# S3220B2.net
KiCad netlist of a schematic drawn in Altium Designer
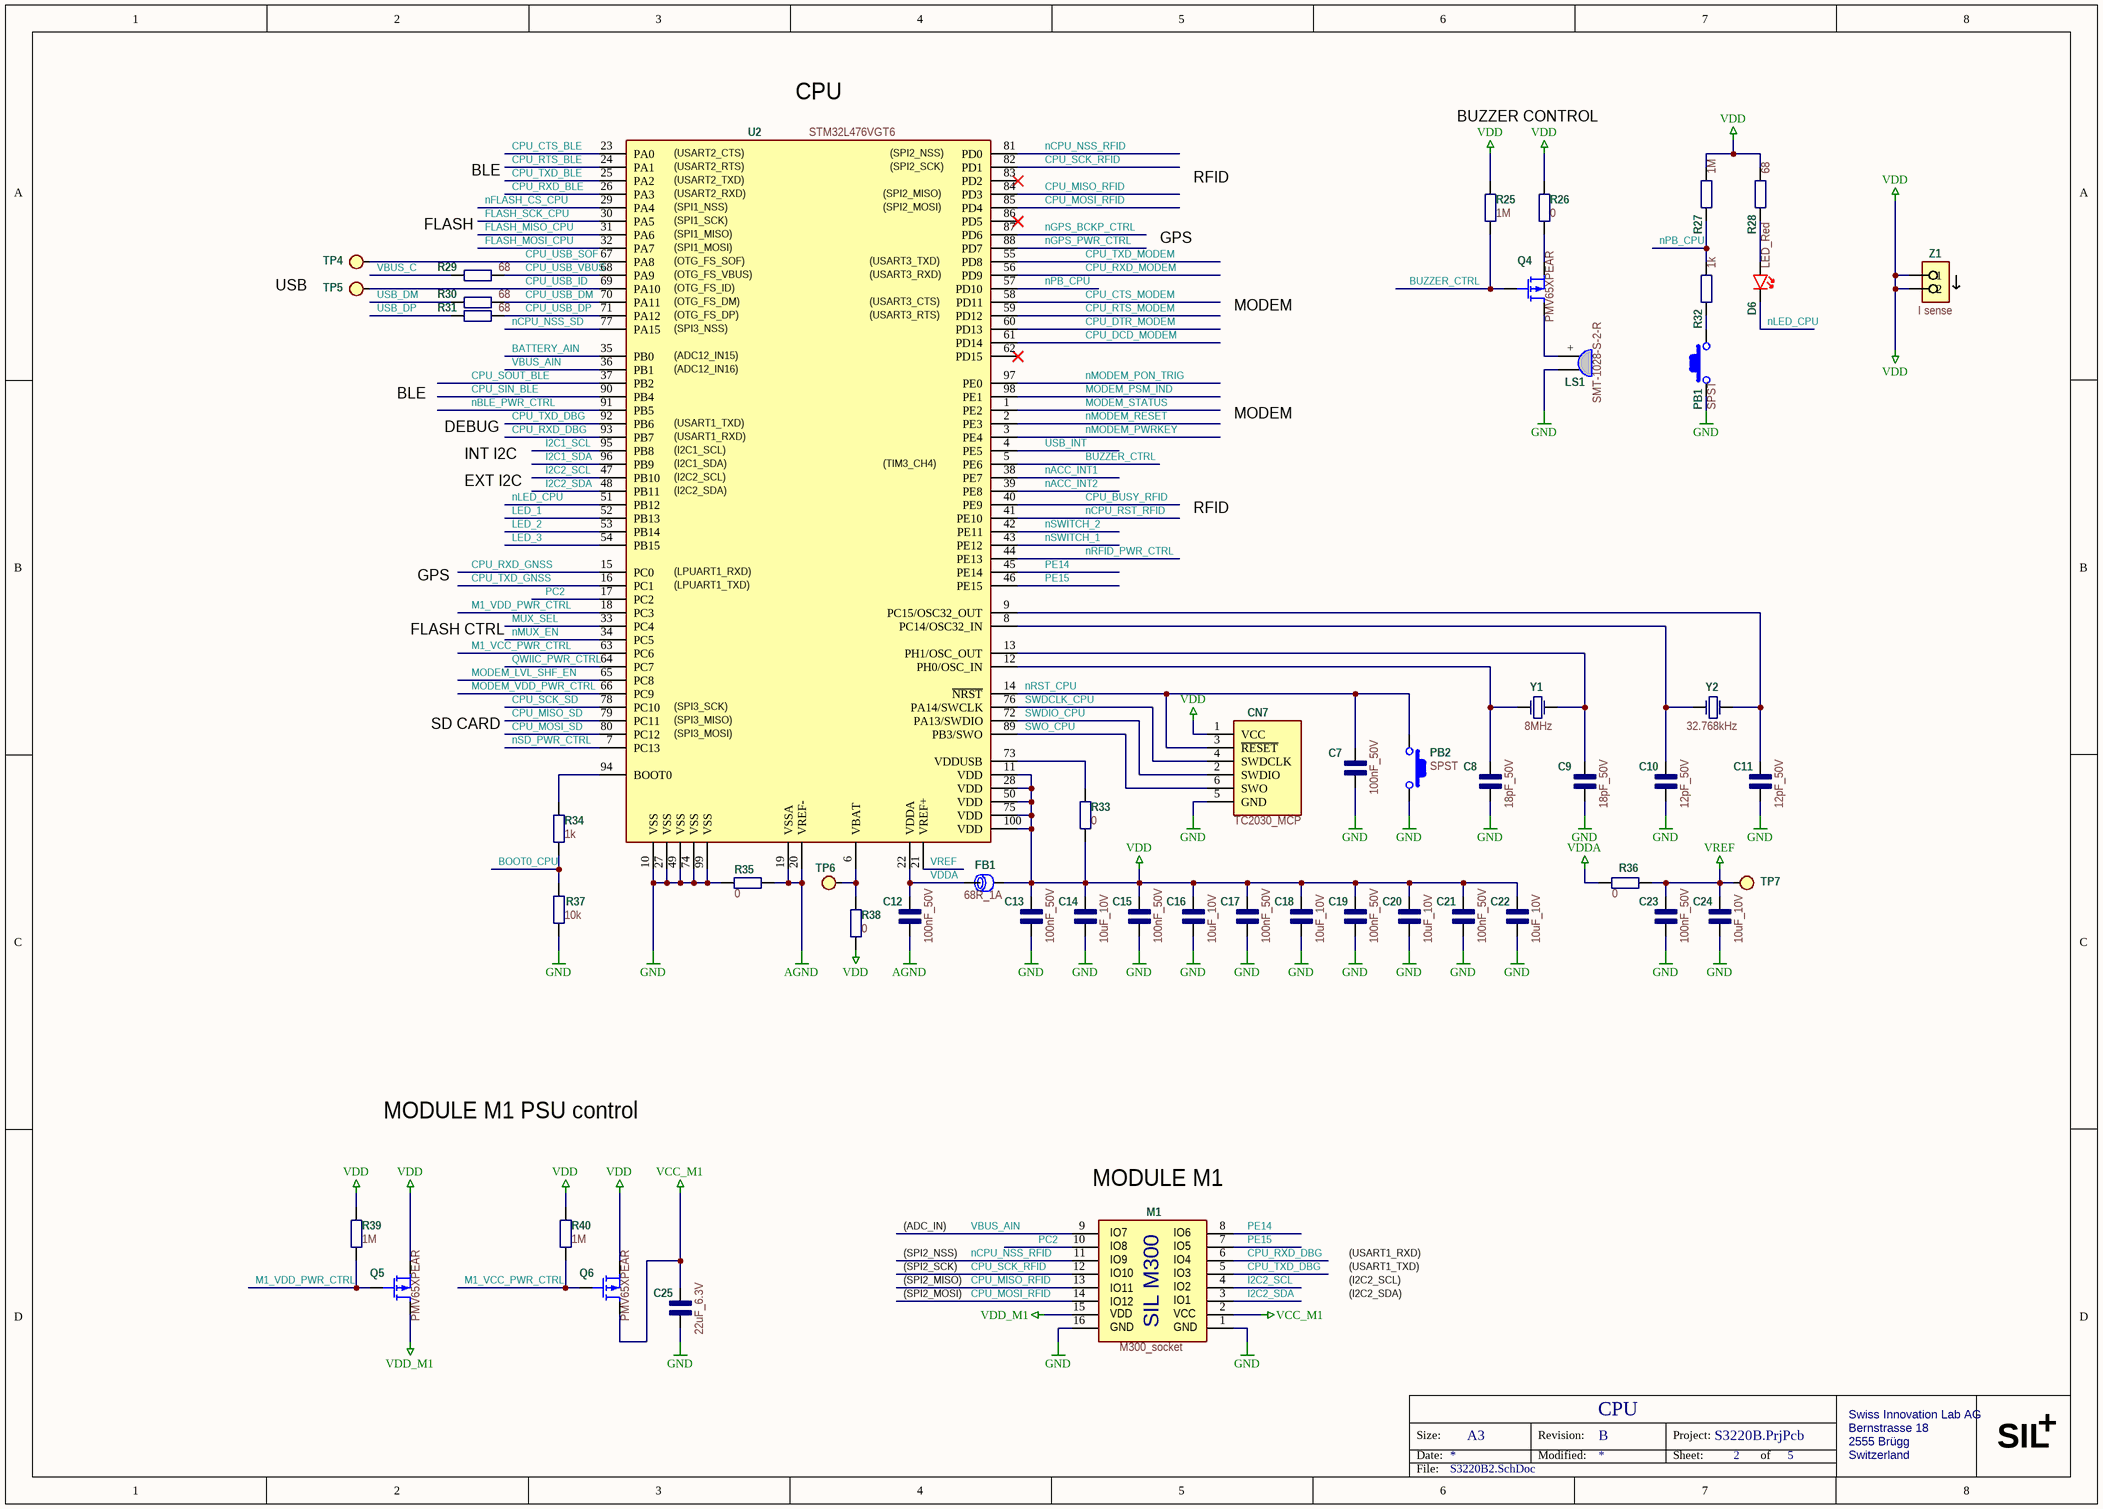
[diagram p0: S3220B2.SchDoc]

(export (version "E")
  (design (tool "Eeschema 10.0.6"))
  (components
    (comp (ref "C7")
      (value "100nF_50V")
      (footprint "SIL:C_0603")
      (description "0.1µF ±10% 50V Ceramic Capacitor X7R 0603 (1608 Metric)")
      (fields
        (field (name "MANUFACTURER") "TDK")
        (field (name "MANUFACTURER PART NUMBER") "C1608X7R1H104K080AA")
      )
      (libsource (lib "SIL") (part "C_100nF_50V"))
    )
    (comp (ref "C8")
      (value "18pF_50V")
      (footprint "SIL:C_0603")
      (description "18pF ±5% 50V Ceramic Capacitor C0G, NP0 0603 (1608 Metric)")
      (fields
        (field (name "MANUFACTURER") "KEMET")
        (field (name "MANUFACTURER PART NUMBER") "C0603C180J5GACTU")
      )
      (libsource (lib "SIL") (part "C_18pF_50V"))
    )
    (comp (ref "C9")
      (value "18pF_50V")
      (footprint "SIL:C_0603")
      (description "18pF ±5% 50V Ceramic Capacitor C0G, NP0 0603 (1608 Metric)")
      (fields
        (field (name "MANUFACTURER") "KEMET")
        (field (name "MANUFACTURER PART NUMBER") "C0603C180J5GACTU")
      )
      (libsource (lib "SIL") (part "C_18pF_50V"))
    )
    (comp (ref "C10")
      (value "12pF_50V")
      (footprint "SIL:C_0603")
      (description "12pF ±1% 50V Ceramic Capacitor C0G, NP0 0603 (1608 Metric)")
      (fields
        (field (name "MANUFACTURER") "Samsung Electro-Mechanics")
        (field (name "MANUFACTURER PART NUMBER") "CL10C120FB8NNNC")
      )
      (libsource (lib "SIL") (part "C_12pF_50V"))
    )
    (comp (ref "C11")
      (value "12pF_50V")
      (footprint "SIL:C_0603")
      (description "12pF ±1% 50V Ceramic Capacitor C0G, NP0 0603 (1608 Metric)")
      (fields
        (field (name "MANUFACTURER") "Samsung Electro-Mechanics")
        (field (name "MANUFACTURER PART NUMBER") "CL10C120FB8NNNC")
      )
      (libsource (lib "SIL") (part "C_12pF_50V"))
    )
    (comp (ref "C12")
      (value "100nF_50V")
      (footprint "SIL:C_0603")
      (description "0.1µF ±10% 50V Ceramic Capacitor X7R 0603 (1608 Metric)")
      (fields
        (field (name "MANUFACTURER") "TDK")
        (field (name "MANUFACTURER PART NUMBER") "C1608X7R1H104K080AA")
      )
      (libsource (lib "SIL") (part "C_100nF_50V"))
    )
    (comp (ref "C13")
      (value "100nF_50V")
      (footprint "SIL:C_0603")
      (description "0.1µF ±10% 50V Ceramic Capacitor X7R 0603 (1608 Metric)")
      (fields
        (field (name "MANUFACTURER") "TDK")
        (field (name "MANUFACTURER PART NUMBER") "C1608X7R1H104K080AA")
      )
      (libsource (lib "SIL") (part "C_100nF_50V"))
    )
    (comp (ref "C14")
      (value "10uF_10V")
      (footprint "SIL:C_0603")
      (description "10µF ±10% 10V Ceramic Capacitor X5R 0603 (1608 Metric)")
      (fields
        (field (name "MANUFACTURER") "Murata Electronics North America")
        (field (name "MANUFACTURER PART NUMBER") "GRM188R61A106KE69D")
      )
      (libsource (lib "SIL") (part "C_10uF_10V"))
    )
    (comp (ref "C15")
      (value "100nF_50V")
      (footprint "SIL:C_0603")
      (description "0.1µF ±10% 50V Ceramic Capacitor X7R 0603 (1608 Metric)")
      (fields
        (field (name "MANUFACTURER") "TDK")
        (field (name "MANUFACTURER PART NUMBER") "C1608X7R1H104K080AA")
      )
      (libsource (lib "SIL") (part "C_100nF_50V"))
    )
    (comp (ref "C16")
      (value "10uF_10V")
      (footprint "SIL:C_0603")
      (description "10µF ±10% 10V Ceramic Capacitor X5R 0603 (1608 Metric)")
      (fields
        (field (name "MANUFACTURER") "Murata Electronics North America")
        (field (name "MANUFACTURER PART NUMBER") "GRM188R61A106KE69D")
      )
      (libsource (lib "SIL") (part "C_10uF_10V"))
    )
    (comp (ref "C17")
      (value "100nF_50V")
      (footprint "SIL:C_0603")
      (description "0.1µF ±10% 50V Ceramic Capacitor X7R 0603 (1608 Metric)")
      (fields
        (field (name "MANUFACTURER") "TDK")
        (field (name "MANUFACTURER PART NUMBER") "C1608X7R1H104K080AA")
      )
      (libsource (lib "SIL") (part "C_100nF_50V"))
    )
    (comp (ref "C18")
      (value "10uF_10V")
      (footprint "SIL:C_0603")
      (description "10µF ±10% 10V Ceramic Capacitor X5R 0603 (1608 Metric)")
      (fields
        (field (name "MANUFACTURER") "Murata Electronics North America")
        (field (name "MANUFACTURER PART NUMBER") "GRM188R61A106KE69D")
      )
      (libsource (lib "SIL") (part "C_10uF_10V"))
    )
    (comp (ref "C19")
      (value "100nF_50V")
      (footprint "SIL:C_0603")
      (description "0.1µF ±10% 50V Ceramic Capacitor X7R 0603 (1608 Metric)")
      (fields
        (field (name "MANUFACTURER") "TDK")
        (field (name "MANUFACTURER PART NUMBER") "C1608X7R1H104K080AA")
      )
      (libsource (lib "SIL") (part "C_100nF_50V"))
    )
    (comp (ref "C20")
      (value "10uF_10V")
      (footprint "SIL:C_0603")
      (description "10µF ±10% 10V Ceramic Capacitor X5R 0603 (1608 Metric)")
      (fields
        (field (name "MANUFACTURER") "Murata Electronics North America")
        (field (name "MANUFACTURER PART NUMBER") "GRM188R61A106KE69D")
      )
      (libsource (lib "SIL") (part "C_10uF_10V"))
    )
    (comp (ref "C21")
      (value "100nF_50V")
      (footprint "SIL:C_0603")
      (description "0.1µF ±10% 50V Ceramic Capacitor X7R 0603 (1608 Metric)")
      (fields
        (field (name "MANUFACTURER") "TDK")
        (field (name "MANUFACTURER PART NUMBER") "C1608X7R1H104K080AA")
      )
      (libsource (lib "SIL") (part "C_100nF_50V"))
    )
    (comp (ref "C22")
      (value "10uF_10V")
      (footprint "SIL:C_0603")
      (description "10µF ±10% 10V Ceramic Capacitor X5R 0603 (1608 Metric)")
      (fields
        (field (name "MANUFACTURER") "Murata Electronics North America")
        (field (name "MANUFACTURER PART NUMBER") "GRM188R61A106KE69D")
      )
      (libsource (lib "SIL") (part "C_10uF_10V"))
    )
    (comp (ref "C23")
      (value "100nF_50V")
      (footprint "SIL:C_0603")
      (description "0.1µF ±10% 50V Ceramic Capacitor X7R 0603 (1608 Metric)")
      (fields
        (field (name "MANUFACTURER") "TDK")
        (field (name "MANUFACTURER PART NUMBER") "C1608X7R1H104K080AA")
      )
      (libsource (lib "SIL") (part "C_100nF_50V"))
    )
    (comp (ref "C24")
      (value "10uF_10V")
      (footprint "SIL:C_0603")
      (description "10µF ±10% 10V Ceramic Capacitor X5R 0603 (1608 Metric)")
      (fields
        (field (name "MANUFACTURER") "Murata Electronics North America")
        (field (name "MANUFACTURER PART NUMBER") "GRM188R61A106KE69D")
      )
      (libsource (lib "SIL") (part "C_10uF_10V"))
    )
    (comp (ref "C25")
      (value "22uF_6.3V")
      (footprint "SIL:C_0603")
      (description "22µF ±20% 6.3V Ceramic Capacitor X5R 0603 (1608 Metric)")
      (fields
        (field (name "MANUFACTURER") "Samsung Electro-Mechanics")
        (field (name "MANUFACTURER PART NUMBER") "CL10A226MQ8NRNC")
      )
      (libsource (lib "SIL") (part "C_22uF_6V3"))
    )
    (comp (ref "CN7")
      (value "TC2030_MCP")
      (footprint "SIL:CN_TC2030-MCP-NL")
      (description "TC2030-MCP-NL")
      (libsource (lib "SIL") (part "CN_TC2030"))
    )
    (comp (ref "D6")
      (value "LED_Red")
      (footprint "LED_0603")
      (description "Red 631nm LED Indication - Discrete 2V 0603")
      (fields
        (field (name "MANUFACTURER") "Lite-On Inc.")
        (field (name "MANUFACTURER PART NUMBER") "LTST-C193KRKT-5A")
      )
      (libsource (lib "SIL") (part "D_LED_R_5mA"))
    )
    (comp (ref "FB1")
      (value "68R_1A")
      (footprint "SIL:L_0603")
      (description "FERRITE BEAD 68 OHM 0603 1LN")
      (fields
        (field (name "MANUFACTURER") "Laird-Signal Integrity Products")
        (field (name "MANUFACTURER PART NUMBER") "MI0603J680R-10")
      )
      (libsource (lib "SIL") (part "FB_68R_1A"))
    )
    (comp (ref "LS1")
      (value "SMT-1028-S-2-R")
      (footprint "LS_SMT-1028-S-2-R")
      (fields (field (name "MANUFACTURER") "PUI Audio, Inc."))
      (libsource (lib "SIL") (part "LS_SMT-1028-S-2-R"))
    )
    (comp (ref "M1")
      (value "M300_socket")
      (footprint "M_M300_socket")
      (description "Module M300 motherboard socket")
      (fields
        (field (name "MANUFACTURER") "Swiss Innovation Lab")
        (field (name "MANUFACTURER PART NUMBER") "M300")
      )
      (libsource (lib "SIL") (part "M_M300_socket"))
    )
    (comp (ref "PB1")
      (value "SPST")
      (footprint "SIL:PB_PTS810")
      (description "Tactile Switch SPST-NO Top Actuated Surface Mount")
      (fields
        (field (name "MANUFACTURER") "C&K")
        (field (name "MANUFACTURER PART NUMBER") "PTS810 SJM 250 SMTR LFS")
      )
      (libsource (lib "SIL") (part "PB_SPST_2.5mm"))
    )
    (comp (ref "PB2")
      (value "SPST")
      (footprint "SIL:PB_PTS810")
      (description "Tactile Switch SPST-NO Top Actuated Surface Mount")
      (fields
        (field (name "MANUFACTURER") "C&K")
        (field (name "MANUFACTURER PART NUMBER") "PTS810 SJM 250 SMTR LFS")
      )
      (libsource (lib "SIL") (part "PB_SPST_2.5mm"))
    )
    (comp (ref "Q4")
      (value "PMV65XPEAR")
      (footprint "U_SOT23-3")
      (description "P-Channel 20V 2.8A (Ta) 480mW (Ta), 6.25W (Tc) Surface Mount TO-236AB (SOT23)")
      (fields (field (name "MANUFACTURER") "Nexperia USA Inc."))
      (libsource (lib "SIL") (part "Q_PMV65"))
    )
    (comp (ref "Q5")
      (value "PMV65XPEAR")
      (footprint "U_SOT23-3")
      (description "P-Channel 20V 2.8A (Ta) 480mW (Ta), 6.25W (Tc) Surface Mount TO-236AB (SOT23)")
      (fields (field (name "MANUFACTURER") "Nexperia USA Inc."))
      (libsource (lib "SIL") (part "Q_PMV65"))
    )
    (comp (ref "Q6")
      (value "PMV65XPEAR")
      (footprint "U_SOT23-3")
      (description "P-Channel 20V 2.8A (Ta) 480mW (Ta), 6.25W (Tc) Surface Mount TO-236AB (SOT23)")
      (fields (field (name "MANUFACTURER") "Nexperia USA Inc."))
      (libsource (lib "SIL") (part "Q_PMV65"))
    )
    (comp (ref "R25")
      (value "1M")
      (footprint "SIL:R_0603")
      (description "1 MOhms ±1% 0.1W, 1/10W Chip Resistor 0603 (1608 Metric) Automotive AEC-Q200 Thick Film")
      (fields
        (field (name "MANUFACTURER") "Panasonic Electronic Components")
        (field (name "MANUFACTURER PART NUMBER") "ERJ-3EKF1004V")
      )
      (libsource (lib "") (part "R_1M_1%_1"))
    )
    (comp (ref "R26")
      (value "0")
      (footprint "SIL:R_0603")
      (description "0 Ohms Jumper 0.1W, 1/10W Chip Resistor 0603 (1608 Metric) Automotive AEC-Q200 Thick Film")
      (fields
        (field (name "MANUFACTURER") "Panasonic Electronic Components")
        (field (name "MANUFACTURER PART NUMBER") "ERJ-3GEY0R00V")
      )
      (libsource (lib "") (part "R_0_1%_2"))
    )
    (comp (ref "R27")
      (value "1M")
      (footprint "SIL:R_0603")
      (description "1 MOhms ±1% 0.1W, 1/10W Chip Resistor 0603 (1608 Metric) Automotive AEC-Q200 Thick Film")
      (fields
        (field (name "MANUFACTURER") "Panasonic Electronic Components")
        (field (name "MANUFACTURER PART NUMBER") "ERJ-3EKF1004V")
      )
      (libsource (lib "SIL") (part "R_1M_1%"))
    )
    (comp (ref "R28")
      (value "68")
      (footprint "SIL:R_0603")
      (description "68 Ohms ±1% 0.1W, 1/10W Chip Resistor 0603 (1608 Metric) Automotive AEC-Q200 Thick Film")
      (fields
        (field (name "MANUFACTURER") "Panasonic Electronic Components")
        (field (name "MANUFACTURER PART NUMBER") "ERJ-3EKF68R0V")
      )
      (libsource (lib "") (part "R_68_1%_1"))
    )
    (comp (ref "R29")
      (value "68")
      (footprint "SIL:R_0603")
      (description "68 Ohms ±1% 0.1W, 1/10W Chip Resistor 0603 (1608 Metric) Automotive AEC-Q200 Thick Film")
      (fields
        (field (name "MANUFACTURER") "Panasonic Electronic Components")
        (field (name "MANUFACTURER PART NUMBER") "ERJ-3EKF68R0V")
      )
      (libsource (lib "SIL") (part "R_68_1%"))
    )
    (comp (ref "R30")
      (value "68")
      (footprint "SIL:R_0603")
      (description "68 Ohms ±1% 0.1W, 1/10W Chip Resistor 0603 (1608 Metric) Automotive AEC-Q200 Thick Film")
      (fields
        (field (name "MANUFACTURER") "Panasonic Electronic Components")
        (field (name "MANUFACTURER PART NUMBER") "ERJ-3EKF68R0V")
      )
      (libsource (lib "SIL") (part "R_68_1%"))
    )
    (comp (ref "R31")
      (value "68")
      (footprint "SIL:R_0603")
      (description "68 Ohms ±1% 0.1W, 1/10W Chip Resistor 0603 (1608 Metric) Automotive AEC-Q200 Thick Film")
      (fields
        (field (name "MANUFACTURER") "Panasonic Electronic Components")
        (field (name "MANUFACTURER PART NUMBER") "ERJ-3EKF68R0V")
      )
      (libsource (lib "SIL") (part "R_68_1%"))
    )
    (comp (ref "R32")
      (value "1k")
      (footprint "SIL:R_0603")
      (description "1 kOhms ±1% 0.1W, 1/10W Chip Resistor 0603 (1608 Metric) Automotive AEC-Q200 Thick Film")
      (fields
        (field (name "MANUFACTURER") "Panasonic Electronic Components")
        (field (name "MANUFACTURER PART NUMBER") "ERJ-3EKF1001V")
      )
      (libsource (lib "SIL") (part "R_1k_1%"))
    )
    (comp (ref "R33")
      (value "0")
      (footprint "SIL:R_0603")
      (description "0 Ohms Jumper 0.1W, 1/10W Chip Resistor 0603 (1608 Metric) Automotive AEC-Q200 Thick Film")
      (fields
        (field (name "MANUFACTURER") "Panasonic Electronic Components")
        (field (name "MANUFACTURER PART NUMBER") "ERJ-3GEY0R00V")
      )
      (libsource (lib "") (part "R_0_1%_2"))
    )
    (comp (ref "R34")
      (value "1k")
      (footprint "SIL:R_0603")
      (description "1 kOhms ±1% 0.1W, 1/10W Chip Resistor 0603 (1608 Metric) Automotive AEC-Q200 Thick Film")
      (fields
        (field (name "MANUFACTURER") "Panasonic Electronic Components")
        (field (name "MANUFACTURER PART NUMBER") "ERJ-3EKF1001V")
      )
      (libsource (lib "SIL") (part "R_1k_1%"))
    )
    (comp (ref "R35")
      (value "0")
      (footprint "SIL:R_0603")
      (description "0 Ohms Jumper 0.1W, 1/10W Chip Resistor 0603 (1608 Metric) Automotive AEC-Q200 Thick Film")
      (fields
        (field (name "MANUFACTURER") "Panasonic Electronic Components")
        (field (name "MANUFACTURER PART NUMBER") "ERJ-3GEY0R00V")
      )
      (libsource (lib "") (part "R_0_1%_1"))
    )
    (comp (ref "R36")
      (value "0")
      (footprint "SIL:R_0603")
      (description "0 Ohms Jumper 0.1W, 1/10W Chip Resistor 0603 (1608 Metric) Automotive AEC-Q200 Thick Film")
      (fields
        (field (name "MANUFACTURER") "Panasonic Electronic Components")
        (field (name "MANUFACTURER PART NUMBER") "ERJ-3GEY0R00V")
      )
      (libsource (lib "") (part "R_0_1%_3"))
    )
    (comp (ref "R37")
      (value "10k")
      (footprint "SIL:R_0603")
      (description "10 kOhms ±1% 0.1W, 1/10W Chip Resistor 0603 (1608 Metric) Automotive AEC-Q200 Thick Film")
      (fields
        (field (name "MANUFACTURER") "Panasonic Electronic Components")
        (field (name "MANUFACTURER PART NUMBER") "ERJ-3EKF1002V")
      )
      (libsource (lib "SIL") (part "R_10k_1%"))
    )
    (comp (ref "R38")
      (value "0")
      (footprint "SIL:R_0603")
      (description "0 Ohms Jumper 0.1W, 1/10W Chip Resistor 0603 (1608 Metric) Automotive AEC-Q200 Thick Film")
      (fields
        (field (name "MANUFACTURER") "Panasonic Electronic Components")
        (field (name "MANUFACTURER PART NUMBER") "ERJ-3GEY0R00V")
      )
      (libsource (lib "SIL") (part "R_0_1%"))
    )
    (comp (ref "R39")
      (value "1M")
      (footprint "SIL:R_0603")
      (description "1 MOhms ±1% 0.1W, 1/10W Chip Resistor 0603 (1608 Metric) Automotive AEC-Q200 Thick Film")
      (fields
        (field (name "MANUFACTURER") "Panasonic Electronic Components")
        (field (name "MANUFACTURER PART NUMBER") "ERJ-3EKF1004V")
      )
      (libsource (lib "") (part "R_1M_1%_1"))
    )
    (comp (ref "R40")
      (value "1M")
      (footprint "SIL:R_0603")
      (description "1 MOhms ±1% 0.1W, 1/10W Chip Resistor 0603 (1608 Metric) Automotive AEC-Q200 Thick Film")
      (fields
        (field (name "MANUFACTURER") "Panasonic Electronic Components")
        (field (name "MANUFACTURER PART NUMBER") "ERJ-3EKF1004V")
      )
      (libsource (lib "SIL") (part "R_1M_1%"))
    )
    (comp (ref "TP4")
      (value "Test point")
      (footprint "SIL:TP_SMD_R1.0mm")
      (fields (field (name "MANUFACTURER") "Swiss Innovation Lab"))
      (libsource (lib "SIL") (part "TP_Test_point"))
    )
    (comp (ref "TP5")
      (value "Test point")
      (footprint "SIL:TP_SMD_R1.0mm")
      (fields (field (name "MANUFACTURER") "Swiss Innovation Lab"))
      (libsource (lib "SIL") (part "TP_Test_point"))
    )
    (comp (ref "TP6")
      (value "Test point")
      (footprint "SIL:TP_SMD_R1.0mm")
      (fields (field (name "MANUFACTURER") "Swiss Innovation Lab"))
      (libsource (lib "SIL") (part "TP_Test_point"))
    )
    (comp (ref "TP7")
      (value "Test point")
      (footprint "SIL:TP_SMD_R1.0mm")
      (fields (field (name "MANUFACTURER") "Swiss Innovation Lab"))
      (libsource (lib "SIL") (part "TP_Test_point"))
    )
    (comp (ref "U2")
      (value "STM32L476VGT6")
      (footprint "SIL:U_100-LQFP")
      (description "ARM® Cortex®-M4 STM32L4 Microcontroller IC 32-Bit 80MHz 1MB (1M x 8) FLASH 100-LQFP (14x14)")
      (fields (field (name "MANUFACTURER") "STMicroelectronics"))
      (libsource (lib "SIL") (part "U_STM32L476"))
    )
    (comp (ref "Y1")
      (value "8MHz")
      (footprint "SIL:Y_ABMM2")
      (description "8MHz ±20ppm Crystal 18pF 72 Ohms 4-SMD, No Lead")
      (fields
        (field (name "MANUFACTURER") "Abracon LLC")
        (field (name "MANUFACTURER PART NUMBER") "ABMM2-8.000MHZ-E2-T")
      )
      (libsource (lib "SIL") (part "Y_8MHz_20ppm"))
    )
    (comp (ref "Y2")
      (value "32.768kHz")
      (footprint "SIL:Y_XTAL-3215")
      (description "32.768kHz ±10ppm Crystal 12.5pF 70 kOhms 2-SMD, No Lead")
      (fields
        (field (name "MANUFACTURER") "ECS Inc.")
        (field (name "MANUFACTURER PART NUMBER") "ECS-.327-12.5-34B-C-TR")
      )
      (libsource (lib "SIL") (part "Y_32kHz_10ppm"))
    )
    (comp (ref "Z1")
      (value "I sense")
      (footprint "Z_I_SENSE")
      (description "2 Positions Header Connector 0.100\" (2.54mm) SMD Gold for current measurement")
      (fields (field (name "MANUFACTURER") "SIL"))
      (libsource (lib "SIL") (part "Z_I_sense"))
    )
  )
  (nets
    (net (code "1") (name "/BATTERY_AIN") (class "Default")
      (node (ref "U2") (pin "35") (pinfunction "PB0_35") (pintype "passive"))
    )
    (net (code "2") (name "/BOOT0_CPU") (class "Default")
      (node (ref "R34") (pin "1") (pinfunction "1_1") (pintype "passive"))
      (node (ref "R37") (pin "2") (pinfunction "2_2") (pintype "passive"))
    )
    (net (code "3") (name "/BUZZER_CTRL") (class "Default")
      (node (ref "Q4") (pin "1") (pinfunction "G_1") (pintype "passive"))
      (node (ref "R25") (pin "1") (pinfunction "1_1") (pintype "passive"))
      (node (ref "U2") (pin "5") (pinfunction "PE6_5") (pintype "passive"))
    )
    (net (code "4") (name "/CPU_BUSY_RFID") (class "Default")
      (node (ref "U2") (pin "40") (pinfunction "PE9_40") (pintype "passive"))
    )
    (net (code "5") (name "/CPU_CTS_BLE") (class "Default")
      (node (ref "U2") (pin "23") (pinfunction "PA0_23") (pintype "passive"))
    )
    (net (code "6") (name "/CPU_CTS_MODEM") (class "Default")
      (node (ref "U2") (pin "58") (pinfunction "PD11_58") (pintype "passive"))
    )
    (net (code "7") (name "/CPU_DCD_MODEM") (class "Default")
      (node (ref "U2") (pin "61") (pinfunction "PD14_61") (pintype "passive"))
    )
    (net (code "8") (name "/CPU_DTR_MODEM") (class "Default")
      (node (ref "U2") (pin "60") (pinfunction "PD13_60") (pintype "passive"))
    )
    (net (code "9") (name "/CPU_MISO_RFID") (class "Default")
      (node (ref "M1") (pin "13") (pinfunction "MISO_13") (pintype "passive"))
      (node (ref "U2") (pin "84") (pinfunction "PD3_84") (pintype "passive"))
    )
    (net (code "10") (name "/CPU_MISO_SD") (class "Default")
      (node (ref "U2") (pin "79") (pinfunction "PC11_79") (pintype "passive"))
    )
    (net (code "11") (name "/CPU_MOSI_RFID") (class "Default")
      (node (ref "M1") (pin "14") (pinfunction "MOSI_14") (pintype "passive"))
      (node (ref "U2") (pin "85") (pinfunction "PD4_85") (pintype "passive"))
    )
    (net (code "12") (name "/CPU_MOSI_SD") (class "Default")
      (node (ref "U2") (pin "80") (pinfunction "PC12_80") (pintype "passive"))
    )
    (net (code "13") (name "/CPU_RTS_BLE") (class "Default")
      (node (ref "U2") (pin "24") (pinfunction "PA1_24") (pintype "passive"))
    )
    (net (code "14") (name "/CPU_RTS_MODEM") (class "Default")
      (node (ref "U2") (pin "59") (pinfunction "PD12_59") (pintype "passive"))
    )
    (net (code "15") (name "/CPU_RXD_BLE") (class "Default")
      (node (ref "U2") (pin "26") (pinfunction "PA3_26") (pintype "passive"))
    )
    (net (code "16") (name "/CPU_RXD_DBG") (class "Default")
      (node (ref "M1") (pin "6") (pinfunction "RX_6") (pintype "passive"))
      (node (ref "U2") (pin "93") (pinfunction "PB7_93") (pintype "passive"))
    )
    (net (code "17") (name "/CPU_RXD_GNSS") (class "Default")
      (node (ref "U2") (pin "15") (pinfunction "PC0_15") (pintype "passive"))
    )
    (net (code "18") (name "/CPU_RXD_MODEM") (class "Default")
      (node (ref "U2") (pin "56") (pinfunction "PD9_56") (pintype "passive"))
    )
    (net (code "19") (name "/CPU_SCK_RFID") (class "Default")
      (node (ref "M1") (pin "12") (pinfunction "SCK_12") (pintype "passive"))
      (node (ref "U2") (pin "82") (pinfunction "PD1_82") (pintype "passive"))
    )
    (net (code "20") (name "/CPU_SCK_SD") (class "Default")
      (node (ref "U2") (pin "78") (pinfunction "PC10_78") (pintype "passive"))
    )
    (net (code "21") (name "/CPU_SIN_BLE") (class "Default")
      (node (ref "U2") (pin "90") (pinfunction "PB4_90") (pintype "passive"))
    )
    (net (code "22") (name "/CPU_SOUT_BLE") (class "Default")
      (node (ref "U2") (pin "37") (pinfunction "PB2_37") (pintype "passive"))
    )
    (net (code "23") (name "/CPU_TXD_BLE") (class "Default")
      (node (ref "U2") (pin "25") (pinfunction "PA2_25") (pintype "passive"))
    )
    (net (code "24") (name "/CPU_TXD_DBG") (class "Default")
      (node (ref "M1") (pin "5") (pinfunction "TX_5") (pintype "passive"))
      (node (ref "U2") (pin "92") (pinfunction "PB6_92") (pintype "passive"))
    )
    (net (code "25") (name "/CPU_TXD_GNSS") (class "Default")
      (node (ref "U2") (pin "16") (pinfunction "PC1_16") (pintype "passive"))
    )
    (net (code "26") (name "/CPU_TXD_MODEM") (class "Default")
      (node (ref "U2") (pin "55") (pinfunction "PD8_55") (pintype "passive"))
    )
    (net (code "27") (name "/CPU_USB_DM") (class "Default")
      (node (ref "R30") (pin "2") (pinfunction "2_2") (pintype "passive"))
      (node (ref "U2") (pin "70") (pinfunction "PA11_70") (pintype "passive"))
    )
    (net (code "28") (name "/CPU_USB_DP") (class "Default")
      (node (ref "R31") (pin "2") (pinfunction "2_2") (pintype "passive"))
      (node (ref "U2") (pin "71") (pinfunction "PA12_71") (pintype "passive"))
    )
    (net (code "29") (name "/CPU_USB_ID") (class "Default")
      (node (ref "TP5") (pin "1") (pinfunction "1_1") (pintype "passive"))
      (node (ref "U2") (pin "69") (pinfunction "PA10_69") (pintype "passive"))
    )
    (net (code "30") (name "/CPU_USB_SOF") (class "Default")
      (node (ref "TP4") (pin "1") (pinfunction "1_1") (pintype "passive"))
      (node (ref "U2") (pin "67") (pinfunction "PA8_67") (pintype "passive"))
    )
    (net (code "31") (name "/CPU_USB_VBUS") (class "Default")
      (node (ref "R29") (pin "2") (pinfunction "2_2") (pintype "passive"))
      (node (ref "U2") (pin "68") (pinfunction "PA9_68") (pintype "passive"))
    )
    (net (code "32") (name "/FLASH_MISO_CPU") (class "Default")
      (node (ref "U2") (pin "31") (pinfunction "PA6_31") (pintype "passive"))
    )
    (net (code "33") (name "/FLASH_MOSI_CPU") (class "Default")
      (node (ref "U2") (pin "32") (pinfunction "PA7_32") (pintype "passive"))
    )
    (net (code "34") (name "/FLASH_SCK_CPU") (class "Default")
      (node (ref "U2") (pin "30") (pinfunction "PA5_30") (pintype "passive"))
    )
    (net (code "35") (name "/I2C1_SCL") (class "Default")
      (node (ref "U2") (pin "95") (pinfunction "PB8_95") (pintype "passive"))
    )
    (net (code "36") (name "/I2C1_SDA") (class "Default")
      (node (ref "U2") (pin "96") (pinfunction "PB9_96") (pintype "passive"))
    )
    (net (code "37") (name "/I2C2_SCL") (class "Default")
      (node (ref "M1") (pin "4") (pinfunction "SCL_4") (pintype "passive"))
      (node (ref "U2") (pin "47") (pinfunction "PB10_47") (pintype "passive"))
    )
    (net (code "38") (name "/I2C2_SDA") (class "Default")
      (node (ref "M1") (pin "3") (pinfunction "SDA_3") (pintype "passive"))
      (node (ref "U2") (pin "48") (pinfunction "PB11_48") (pintype "passive"))
    )
    (net (code "39") (name "/LED_1") (class "Default")
      (node (ref "U2") (pin "52") (pinfunction "PB13_52") (pintype "passive"))
    )
    (net (code "40") (name "/LED_2") (class "Default")
      (node (ref "U2") (pin "53") (pinfunction "PB14_53") (pintype "passive"))
    )
    (net (code "41") (name "/LED_3") (class "Default")
      (node (ref "U2") (pin "54") (pinfunction "PB15_54") (pintype "passive"))
    )
    (net (code "42") (name "/M1_VCC_PWR_CTRL") (class "Default")
      (node (ref "Q6") (pin "1") (pinfunction "G_1") (pintype "passive"))
      (node (ref "R40") (pin "2") (pinfunction "2_2") (pintype "passive"))
      (node (ref "U2") (pin "63") (pinfunction "PC6_63") (pintype "passive"))
    )
    (net (code "43") (name "/M1_VDD_PWR_CTRL") (class "Default")
      (node (ref "Q5") (pin "1") (pinfunction "G_1") (pintype "passive"))
      (node (ref "R39") (pin "1") (pinfunction "1_1") (pintype "passive"))
      (node (ref "U2") (pin "18") (pinfunction "PC3_18") (pintype "passive"))
    )
    (net (code "44") (name "/MODEM_LVL_SHF_EN") (class "Default")
      (node (ref "U2") (pin "65") (pinfunction "PC8_65") (pintype "passive"))
    )
    (net (code "45") (name "/MODEM_PSM_IND") (class "Default")
      (node (ref "U2") (pin "98") (pinfunction "PE1_98") (pintype "passive"))
    )
    (net (code "46") (name "/MODEM_STATUS") (class "Default")
      (node (ref "U2") (pin "1") (pinfunction "PE2_1") (pintype "passive"))
    )
    (net (code "47") (name "/MODEM_VDD_PWR_CTRL") (class "Default")
      (node (ref "U2") (pin "66") (pinfunction "PC9_66") (pintype "passive"))
    )
    (net (code "48") (name "/MUX_SEL") (class "Default")
      (node (ref "U2") (pin "33") (pinfunction "PC4_33") (pintype "passive"))
    )
    (net (code "49") (name "/PC2") (class "Default")
      (node (ref "M1") (pin "10") (pinfunction "RST_10") (pintype "passive"))
      (node (ref "U2") (pin "17") (pinfunction "PC2_17") (pintype "passive"))
    )
    (net (code "50") (name "/PE14") (class "Default")
      (node (ref "M1") (pin "8") (pinfunction "PWM_8") (pintype "passive"))
      (node (ref "U2") (pin "45") (pinfunction "PE14_45") (pintype "passive"))
    )
    (net (code "51") (name "/PE15") (class "Default")
      (node (ref "M1") (pin "7") (pinfunction "INT_7") (pintype "passive"))
      (node (ref "U2") (pin "46") (pinfunction "PE15_46") (pintype "passive"))
    )
    (net (code "52") (name "/QWIIC_PWR_CTRL") (class "Default")
      (node (ref "U2") (pin "64") (pinfunction "PC7_64") (pintype "passive"))
    )
    (net (code "53") (name "/SWDCLK_CPU") (class "Default")
      (node (ref "CN7") (pin "4") (pinfunction "SWDCLK_4") (pintype "passive"))
      (node (ref "U2") (pin "76") (pinfunction "PA14/SWCLK_76") (pintype "passive"))
    )
    (net (code "54") (name "/SWDIO_CPU") (class "Default")
      (node (ref "CN7") (pin "2") (pinfunction "SWDIO_2") (pintype "passive"))
      (node (ref "U2") (pin "72") (pinfunction "PA13/SWDIO_72") (pintype "passive"))
    )
    (net (code "55") (name "/SWO_CPU") (class "Default")
      (node (ref "CN7") (pin "6") (pinfunction "SWO_6") (pintype "passive"))
      (node (ref "U2") (pin "89") (pinfunction "PB3/SWO_89") (pintype "passive"))
    )
    (net (code "56") (name "/USB_DM") (class "Default")
      (node (ref "R30") (pin "1") (pinfunction "1_1") (pintype "passive"))
    )
    (net (code "57") (name "/USB_DP") (class "Default")
      (node (ref "R31") (pin "1") (pinfunction "1_1") (pintype "passive"))
    )
    (net (code "58") (name "/USB_INT") (class "Default")
      (node (ref "U2") (pin "4") (pinfunction "PE5_4") (pintype "passive"))
    )
    (net (code "59") (name "/VBUS_AIN") (class "Default")
      (node (ref "M1") (pin "9") (pinfunction "AN_9") (pintype "passive"))
      (node (ref "U2") (pin "36") (pinfunction "PB1_36") (pintype "passive"))
    )
    (net (code "60") (name "/VBUS_C") (class "Default")
      (node (ref "R29") (pin "1") (pinfunction "1_1") (pintype "passive"))
    )
    (net (code "61") (name "/nACC_INT1") (class "Default")
      (node (ref "U2") (pin "38") (pinfunction "PE7_38") (pintype "passive"))
    )
    (net (code "62") (name "/nACC_INT2") (class "Default")
      (node (ref "U2") (pin "39") (pinfunction "PE8_39") (pintype "passive"))
    )
    (net (code "63") (name "/nBLE_PWR_CTRL") (class "Default")
      (node (ref "U2") (pin "91") (pinfunction "PB5_91") (pintype "passive"))
    )
    (net (code "64") (name "/nCPU_NSS_RFID") (class "Default")
      (node (ref "M1") (pin "11") (pinfunction "CS_11") (pintype "passive"))
      (node (ref "U2") (pin "81") (pinfunction "PD0_81") (pintype "passive"))
    )
    (net (code "65") (name "/nCPU_NSS_SD") (class "Default")
      (node (ref "U2") (pin "77") (pinfunction "PA15_77") (pintype "passive"))
    )
    (net (code "66") (name "/nCPU_RST_RFID") (class "Default")
      (node (ref "U2") (pin "41") (pinfunction "PE10_41") (pintype "passive"))
    )
    (net (code "67") (name "/nFLASH_CS_CPU") (class "Default")
      (node (ref "U2") (pin "29") (pinfunction "PA4_29") (pintype "passive"))
    )
    (net (code "68") (name "/nGPS_BCKP_CTRL") (class "Default")
      (node (ref "U2") (pin "87") (pinfunction "PD6_87") (pintype "passive"))
    )
    (net (code "69") (name "/nGPS_PWR_CTRL") (class "Default")
      (node (ref "U2") (pin "88") (pinfunction "PD7_88") (pintype "passive"))
    )
    (net (code "70") (name "/nLED_CPU") (class "Default")
      (node (ref "D6") (pin "2") (pinfunction "K_2") (pintype "passive"))
      (node (ref "U2") (pin "51") (pinfunction "PB12_51") (pintype "passive"))
    )
    (net (code "71") (name "/nMODEM_PON_TRIG") (class "Default")
      (node (ref "U2") (pin "97") (pinfunction "PE0_97") (pintype "passive"))
    )
    (net (code "72") (name "/nMODEM_PWRKEY") (class "Default")
      (node (ref "U2") (pin "3") (pinfunction "PE4_3") (pintype "passive"))
    )
    (net (code "73") (name "/nMODEM_RESET") (class "Default")
      (node (ref "U2") (pin "2") (pinfunction "PE3_2") (pintype "passive"))
    )
    (net (code "74") (name "/nMUX_EN") (class "Default")
      (node (ref "U2") (pin "34") (pinfunction "PC5_34") (pintype "passive"))
    )
    (net (code "75") (name "/nPB_CPU") (class "Default")
      (node (ref "R27") (pin "2") (pinfunction "2_2") (pintype "passive"))
      (node (ref "R32") (pin "2") (pinfunction "2_2") (pintype "passive"))
      (node (ref "U2") (pin "57") (pinfunction "PD10_57") (pintype "passive"))
    )
    (net (code "76") (name "/nRFID_PWR_CTRL") (class "Default")
      (node (ref "U2") (pin "44") (pinfunction "PE13_44") (pintype "passive"))
    )
    (net (code "77") (name "/nRST_CPU") (class "Default")
      (node (ref "C7") (pin "2") (pintype "passive"))
      (node (ref "CN7") (pin "3") (pinfunction "~{RESET}_3") (pintype "passive"))
      (node (ref "PB2") (pin "2") (pinfunction "2_2") (pintype "passive"))
      (node (ref "U2") (pin "14") (pinfunction "~{NRST}_14") (pintype "passive"))
    )
    (net (code "78") (name "/nSD_PWR_CTRL") (class "Default")
      (node (ref "U2") (pin "7") (pinfunction "PC13_7") (pintype "passive"))
    )
    (net (code "79") (name "/nSWITCH_1") (class "Default")
      (node (ref "U2") (pin "43") (pinfunction "PE12_43") (pintype "passive"))
    )
    (net (code "80") (name "/nSWITCH_2") (class "Default")
      (node (ref "U2") (pin "42") (pinfunction "PE11_42") (pintype "passive"))
    )
    (net (code "81") (name "AGND") (class "Default")
      (node (ref "C12") (pin "1") (pintype "passive"))
      (node (ref "R35") (pin "2") (pinfunction "2_2") (pintype "passive"))
      (node (ref "U2") (pin "19") (pinfunction "VSSA_19") (pintype "passive"))
      (node (ref "U2") (pin "20") (pinfunction "VREF-_20") (pintype "passive"))
    )
    (net (code "82") (name "GND") (class "Default")
      (node (ref "C10") (pin "1") (pintype "passive"))
      (node (ref "C11") (pin "1") (pintype "passive"))
      (node (ref "C13") (pin "1") (pintype "passive"))
      (node (ref "C14") (pin "1") (pintype "passive"))
      (node (ref "C15") (pin "1") (pintype "passive"))
      (node (ref "C16") (pin "1") (pintype "passive"))
      (node (ref "C17") (pin "1") (pintype "passive"))
      (node (ref "C18") (pin "1") (pintype "passive"))
      (node (ref "C19") (pin "1") (pintype "passive"))
      (node (ref "C20") (pin "1") (pintype "passive"))
      (node (ref "C21") (pin "1") (pintype "passive"))
      (node (ref "C22") (pin "1") (pintype "passive"))
      (node (ref "C23") (pin "1") (pintype "passive"))
      (node (ref "C24") (pin "1") (pintype "passive"))
      (node (ref "C25") (pin "1") (pintype "passive"))
      (node (ref "C7") (pin "1") (pintype "passive"))
      (node (ref "C8") (pin "1") (pintype "passive"))
      (node (ref "C9") (pin "1") (pintype "passive"))
      (node (ref "CN7") (pin "5") (pinfunction "GND_5") (pintype "passive"))
      (node (ref "LS1") (pin "2") (pinfunction "-_2") (pintype "passive"))
      (node (ref "M1") (pin "1") (pinfunction "GND_1") (pintype "passive"))
      (node (ref "M1") (pin "16") (pinfunction "GND_16") (pintype "passive"))
      (node (ref "PB1") (pin "2") (pinfunction "2_2") (pintype "passive"))
      (node (ref "PB2") (pin "1") (pinfunction "1_1") (pintype "passive"))
      (node (ref "R35") (pin "1") (pinfunction "1_1") (pintype "passive"))
      (node (ref "R37") (pin "1") (pinfunction "1_1") (pintype "passive"))
      (node (ref "U2") (pin "10") (pinfunction "VSS_10") (pintype "passive"))
      (node (ref "U2") (pin "27") (pinfunction "VSS_27") (pintype "passive"))
      (node (ref "U2") (pin "49") (pinfunction "VSS_49") (pintype "passive"))
      (node (ref "U2") (pin "74") (pinfunction "VSS_74") (pintype "passive"))
      (node (ref "U2") (pin "99") (pinfunction "VSS_99") (pintype "passive"))
    )
    (net (code "83") (name "Net-(D6-A)") (class "Default")
      (node (ref "D6") (pin "1") (pinfunction "A_1") (pintype "passive"))
      (node (ref "R28") (pin "1") (pinfunction "1_1") (pintype "passive"))
    )
    (net (code "84") (name "Net-(LS1-+)") (class "Default")
      (node (ref "LS1") (pin "1") (pinfunction "+_1") (pintype "passive"))
      (node (ref "Q4") (pin "3") (pinfunction "D_3") (pintype "passive"))
    )
    (net (code "85") (name "Net-(PB1-Pad1)") (class "Default")
      (node (ref "PB1") (pin "1") (pinfunction "1_1") (pintype "passive"))
      (node (ref "R32") (pin "1") (pinfunction "1_1") (pintype "passive"))
    )
    (net (code "86") (name "Net-(Q4-S)") (class "Default")
      (node (ref "Q4") (pin "2") (pinfunction "S_2") (pintype "passive"))
      (node (ref "R26") (pin "2") (pinfunction "2_2") (pintype "passive"))
    )
    (net (code "87") (name "Net-(U2-BOOT0)") (class "Default")
      (node (ref "R34") (pin "2") (pinfunction "2_2") (pintype "passive"))
      (node (ref "U2") (pin "94") (pinfunction "BOOT0_94") (pintype "passive"))
    )
    (net (code "88") (name "Net-(U2-PC14{slash}OSC32_IN)") (class "Default")
      (node (ref "C10") (pin "2") (pintype "passive"))
      (node (ref "U2") (pin "8") (pinfunction "PC14/OSC32_IN_8") (pintype "passive"))
      (node (ref "Y2") (pin "1") (pinfunction "inp_1") (pintype "passive"))
    )
    (net (code "89") (name "Net-(U2-PC15{slash}OSC32_OUT)") (class "Default")
      (node (ref "C11") (pin "2") (pintype "passive"))
      (node (ref "U2") (pin "9") (pinfunction "PC15/OSC32_OUT_9") (pintype "passive"))
      (node (ref "Y2") (pin "2") (pinfunction "out_2") (pintype "passive"))
    )
    (net (code "90") (name "Net-(U2-PH0{slash}OSC_IN)") (class "Default")
      (node (ref "C8") (pin "2") (pintype "passive"))
      (node (ref "U2") (pin "12") (pinfunction "PH0/OSC_IN_12") (pintype "passive"))
      (node (ref "Y1") (pin "1") (pinfunction "inp_1") (pintype "passive"))
    )
    (net (code "91") (name "Net-(U2-PH1{slash}OSC_OUT)") (class "Default")
      (node (ref "C9") (pin "2") (pintype "passive"))
      (node (ref "U2") (pin "13") (pinfunction "PH1/OSC_OUT_13") (pintype "passive"))
      (node (ref "Y1") (pin "3") (pinfunction "out_3") (pintype "passive"))
    )
    (net (code "92") (name "Net-(U2-VBAT)") (class "Default")
      (node (ref "R38") (pin "2") (pinfunction "2_2") (pintype "passive"))
      (node (ref "TP6") (pin "1") (pinfunction "1_1") (pintype "passive"))
      (node (ref "U2") (pin "6") (pinfunction "VBAT_6") (pintype "passive"))
    )
    (net (code "93") (name "Net-(U2-VDDUSB)") (class "Default")
      (node (ref "R33") (pin "1") (pinfunction "1_1") (pintype "passive"))
      (node (ref "U2") (pin "73") (pinfunction "VDDUSB_73") (pintype "power_in"))
    )
    (net (code "94") (name "VCC_M1") (class "Default")
      (node (ref "C25") (pin "2") (pintype "passive"))
      (node (ref "M1") (pin "2") (pinfunction "5V_2") (pintype "passive"))
      (node (ref "Q6") (pin "3") (pinfunction "D_3") (pintype "passive"))
    )
    (net (code "95") (name "VDD") (class "Default")
      (node (ref "C13") (pin "2") (pintype "passive"))
      (node (ref "C14") (pin "2") (pintype "passive"))
      (node (ref "C15") (pin "2") (pintype "passive"))
      (node (ref "C16") (pin "2") (pintype "passive"))
      (node (ref "C17") (pin "2") (pintype "passive"))
      (node (ref "C18") (pin "2") (pintype "passive"))
      (node (ref "C19") (pin "2") (pintype "passive"))
      (node (ref "C20") (pin "2") (pintype "passive"))
      (node (ref "C21") (pin "2") (pintype "passive"))
      (node (ref "C22") (pin "2") (pintype "passive"))
      (node (ref "CN7") (pin "1") (pinfunction "VCC_1") (pintype "power_in"))
      (node (ref "FB1") (pin "2") (pintype "passive"))
      (node (ref "Q5") (pin "2") (pinfunction "S_2") (pintype "passive"))
      (node (ref "Q6") (pin "2") (pinfunction "S_2") (pintype "passive"))
      (node (ref "R25") (pin "2") (pinfunction "2_2") (pintype "passive"))
      (node (ref "R26") (pin "1") (pinfunction "1_1") (pintype "passive"))
      (node (ref "R27") (pin "1") (pinfunction "1_1") (pintype "passive"))
      (node (ref "R28") (pin "2") (pinfunction "2_2") (pintype "passive"))
      (node (ref "R33") (pin "2") (pinfunction "2_2") (pintype "passive"))
      (node (ref "R38") (pin "1") (pinfunction "1_1") (pintype "passive"))
      (node (ref "R39") (pin "2") (pinfunction "2_2") (pintype "passive"))
      (node (ref "R40") (pin "1") (pinfunction "1_1") (pintype "passive"))
      (node (ref "U2") (pin "100") (pinfunction "VDD_100") (pintype "power_in"))
      (node (ref "U2") (pin "11") (pinfunction "VDD_11") (pintype "power_in"))
      (node (ref "U2") (pin "28") (pinfunction "VDD_28") (pintype "power_in"))
      (node (ref "U2") (pin "50") (pinfunction "VDD_50") (pintype "power_in"))
      (node (ref "U2") (pin "75") (pinfunction "VDD_75") (pintype "power_in"))
      (node (ref "Z1") (pin "1") (pinfunction "1_1") (pintype "passive"))
      (node (ref "Z1") (pin "2") (pinfunction "2_2") (pintype "passive"))
    )
    (net (code "96") (name "VDDA") (class "Default")
      (node (ref "C12") (pin "2") (pintype "passive"))
      (node (ref "FB1") (pin "1") (pintype "passive"))
      (node (ref "R36") (pin "2") (pinfunction "2_2") (pintype "passive"))
      (node (ref "U2") (pin "22") (pinfunction "VDDA_22") (pintype "power_in"))
    )
    (net (code "97") (name "VDD_M1") (class "Default")
      (node (ref "M1") (pin "15") (pinfunction "3.3V_15") (pintype "passive"))
      (node (ref "Q5") (pin "3") (pinfunction "D_3") (pintype "passive"))
    )
    (net (code "98") (name "VREF") (class "Default")
      (node (ref "C23") (pin "2") (pintype "passive"))
      (node (ref "C24") (pin "2") (pintype "passive"))
      (node (ref "R36") (pin "1") (pinfunction "1_1") (pintype "passive"))
      (node (ref "TP7") (pin "1") (pinfunction "1_1") (pintype "passive"))
      (node (ref "U2") (pin "21") (pinfunction "VREF+_21") (pintype "passive"))
    )
    (net (code "99") (name "unconnected-(U2-PD2-Pad83)") (class "Default")
      (node (ref "U2") (pin "83") (pinfunction "PD2_83") (pintype "passive+no_connect"))
    )
    (net (code "100") (name "unconnected-(U2-PD5-Pad86)") (class "Default")
      (node (ref "U2") (pin "86") (pinfunction "PD5_86") (pintype "passive+no_connect"))
    )
    (net (code "101") (name "unconnected-(U2-PD15-Pad62)") (class "Default")
      (node (ref "U2") (pin "62") (pinfunction "PD15_62") (pintype "passive+no_connect"))
    )
  )
)
